# Power.net
KiCad netlist of a schematic drawn in Altium Designer
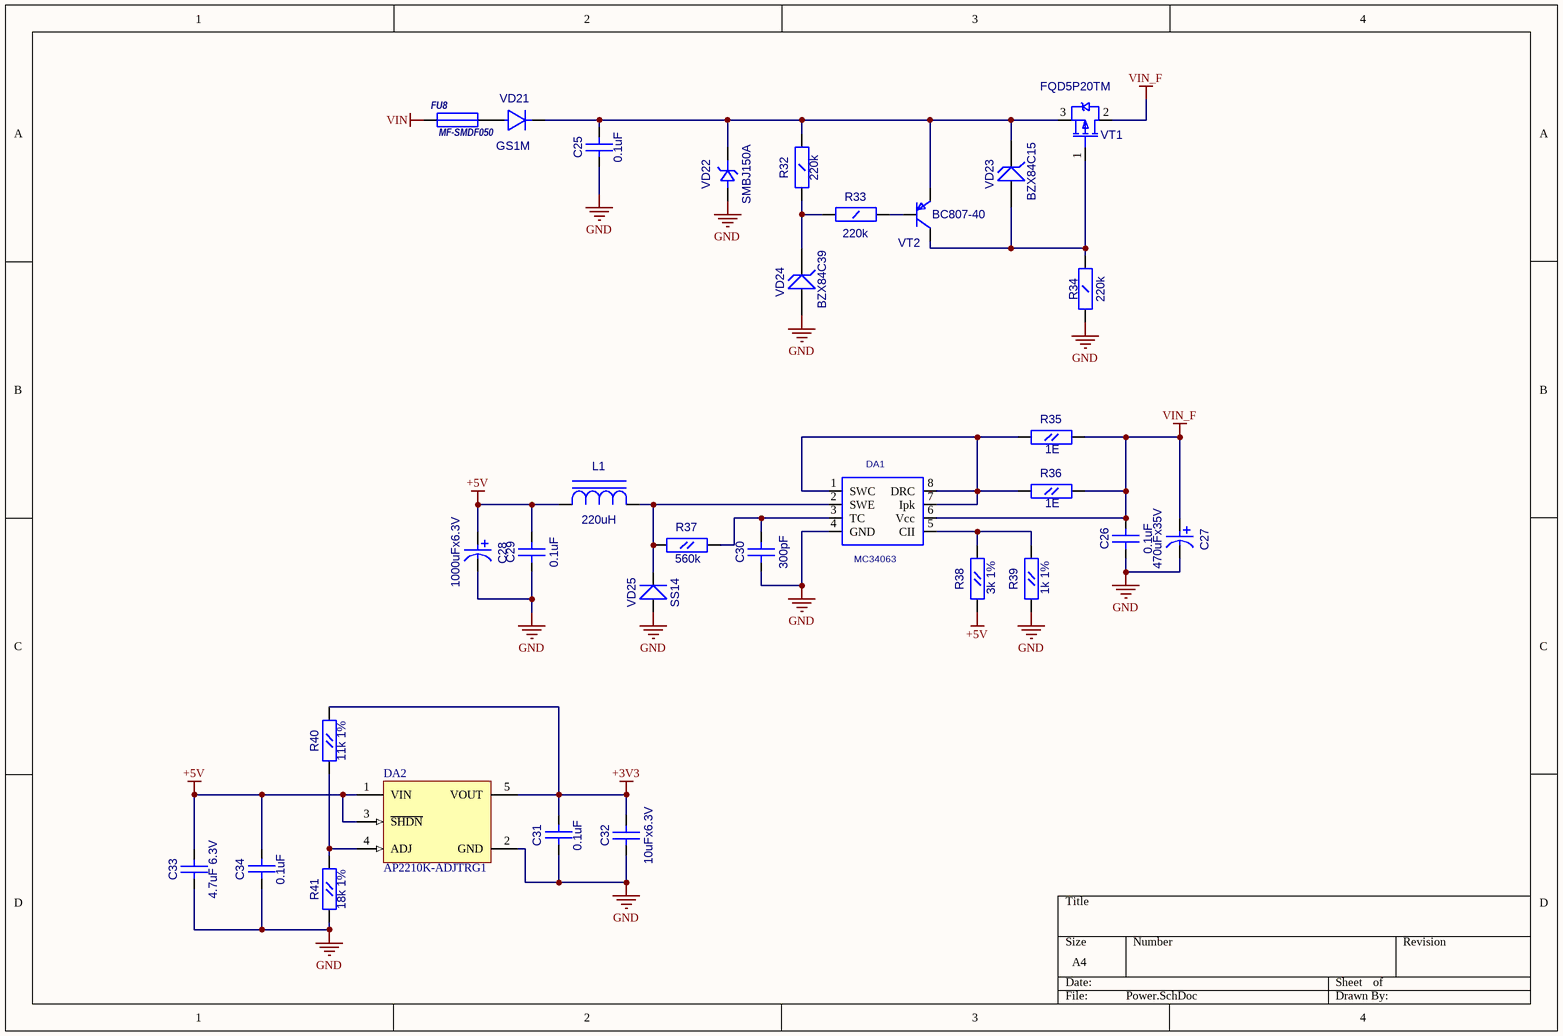
[diagram p0: Power.SchDoc]

(export (version "E")
  (design (tool "Eeschema 10.0.6"))
  (components
    (comp (ref "C25")
      (value "0.1uF")
      (footprint "CC1206")
      (description "CC1206")
      (libsource (lib "gprs_modem_2") (part "CC1206"))
    )
    (comp (ref "C26")
      (value "0.1uF")
      (footprint "CC0603")
      (description "CC0603")
      (libsource (lib "gprs_modem_2") (part "CC0603"))
    )
    (comp (ref "C27")
      (value "470uFx35V")
      (footprint "CC16X10_CAP0.5(1)(Primary)")
      (description "CAP0.5(1)")
      (libsource (lib "gprs_modem_2") (part "CAP0.5(1)"))
    )
    (comp (ref "C28")
      (value "1000uFx6.3V")
      (footprint "CC8X3.5")
      (description "CAP0.35")
      (libsource (lib "gprs_modem_2") (part "CAP0.35"))
    )
    (comp (ref "C29")
      (value "0.1uF")
      (footprint "CC0603")
      (description "CC0603")
      (libsource (lib "gprs_modem_2") (part "CC0603"))
    )
    (comp (ref "C30")
      (value "300pF")
      (footprint "CC0603")
      (description "CC0603")
      (libsource (lib "gprs_modem_2") (part "CC0603"))
    )
    (comp (ref "C31")
      (value "0.1uF")
      (footprint "CC0603")
      (description "CC0603")
      (libsource (lib "gprs_modem_2") (part "CC0603"))
    )
    (comp (ref "C32")
      (value "10uFx6.3V")
      (footprint "CC0805")
      (description "CC0805")
      (libsource (lib "gprs_modem_2") (part "CC0805"))
    )
    (comp (ref "C33")
      (value "4.7uF 6.3V")
      (footprint "CC0805")
      (description "CC0805")
      (libsource (lib "gprs_modem_2") (part "CC0805"))
    )
    (comp (ref "C34")
      (value "0.1uF")
      (footprint "CC0603")
      (description "CC0603")
      (libsource (lib "gprs_modem_2") (part "CC0603"))
    )
    (comp (ref "DA1") (value "MC34063") (footprint "SO-8") (libsource (lib "Schetchik") (part "MC34063")))
    (comp (ref "DA2")
      (value "AP2210K-ADJTRG1")
      (footprint "SOT23-5")
      (fields (field (name "PUBLISHER") "Altium Limited"))
      (libsource (lib "gprs_modem_2") (part "MCP1824T-ADJE/OT"))
    )
    (comp (ref "FU8")
      (value "MF-SMDF050")
      (footprint "MF-SMDF")
      (description "MF-SMDF")
      (libsource (lib "gprs_modem_2") (part "MF-SMDF"))
    )
    (comp (ref "L1")
      (value "220uH")
      (footprint "SDR0805")
      (description "SDR0805")
      (libsource (lib "gprs_modem_2") (part "SDR0805"))
    )
    (comp (ref "R32")
      (value "220k")
      (footprint "RC1206")
      (description "RC1206")
      (libsource (lib "gprs_modem_2") (part "RC1206"))
    )
    (comp (ref "R33")
      (value "220k")
      (footprint "RC1206")
      (description "RC1206")
      (libsource (lib "gprs_modem_2") (part "RC1206"))
    )
    (comp (ref "R34")
      (value "220k")
      (footprint "RC1206")
      (description "RC1206")
      (libsource (lib "gprs_modem_2") (part "RC1206"))
    )
    (comp (ref "R35")
      (value "1E")
      (footprint "RC0805")
      (description "RC0805")
      (libsource (lib "gprs_modem_2") (part "RC0805"))
    )
    (comp (ref "R36")
      (value "1E")
      (footprint "RC0805")
      (description "RC0805")
      (libsource (lib "gprs_modem_2") (part "RC0805"))
    )
    (comp (ref "R37")
      (value "560k")
      (footprint "RC0603")
      (description "RC0603")
      (libsource (lib "gprs_modem_2") (part "RC0603"))
    )
    (comp (ref "R38")
      (value "3k 1%")
      (footprint "RC0603")
      (description "RC0603")
      (libsource (lib "gprs_modem_2") (part "RC0603"))
    )
    (comp (ref "R39")
      (value "1k 1%")
      (footprint "RC0603")
      (description "RC0603")
      (libsource (lib "gprs_modem_2") (part "RC0603"))
    )
    (comp (ref "R40")
      (value "11k 1%")
      (footprint "RC0603")
      (description "RC0603")
      (libsource (lib "gprs_modem_2") (part "RC0603"))
    )
    (comp (ref "R41")
      (value "18k 1%")
      (footprint "RC0603")
      (description "RC0603")
      (libsource (lib "gprs_modem_2") (part "RC0603"))
    )
    (comp (ref "VD21") (value "GS1M") (footprint "SMA") (libsource (lib "gprs_modem") (part "GS1M")))
    (comp (ref "VD22")
      (value "SMBJ150A")
      (footprint "SMB")
      (description "SMBJ")
      (libsource (lib "gprs_modem_2") (part "SMBJ"))
    )
    (comp (ref "VD23")
      (value "BZX84C15")
      (footprint "SOT-23(123)")
      (description "Zener Voltage Regulator Diode")
      (libsource (lib "gprs_modem_2") (part "BZX84"))
    )
    (comp (ref "VD24")
      (value "BZX84C39")
      (footprint "SOT-23(123)")
      (description "Zener Voltage Regulator Diode")
      (libsource (lib "gprs_modem_2") (part "BZX84"))
    )
    (comp (ref "VD25")
      (value "SS14")
      (footprint "SMA")
      (description "Schottky Rectifier")
      (libsource (lib "gprs_modem_2") (part "SS14"))
    )
    (comp (ref "VT1")
      (value "FQD5P20TM")
      (footprint "D-PAK(TO-252AA)")
      (description "HEXFET Power MOSFET")
      (libsource (lib "gprs_modem_2") (part "IRFR9220"))
    )
    (comp (ref "VT2")
      (value "BC807-40")
      (footprint "SOT-23(123)")
      (description "BC857B")
      (libsource (lib "gprs_modem") (part "BC857B"))
    )
  )
  (nets
    (net (code "1") (name "+3V3") (class "Default")
      (node (ref "C31") (pin "1") (pinfunction "A_1") (pintype "passive"))
      (node (ref "C32") (pin "2") (pinfunction "B_2") (pintype "passive"))
      (node (ref "DA2") (pin "5") (pinfunction "VOUT_5") (pintype "power_in"))
      (node (ref "R40") (pin "2") (pinfunction "B_2") (pintype "passive"))
    )
    (net (code "2") (name "+5V") (class "Default")
      (node (ref "C28") (pin "1") (pintype "passive"))
      (node (ref "C29") (pin "2") (pinfunction "B_2") (pintype "passive"))
      (node (ref "C33") (pin "2") (pinfunction "B_2") (pintype "passive"))
      (node (ref "C34") (pin "1") (pinfunction "A_1") (pintype "passive"))
      (node (ref "DA2") (pin "1") (pinfunction "VIN_1") (pintype "power_in"))
      (node (ref "DA2") (pin "3") (pinfunction "~{SHDN}_3") (pintype "input"))
      (node (ref "L1") (pin "1") (pinfunction "C_1") (pintype "passive"))
      (node (ref "R38") (pin "1") (pinfunction "A_1") (pintype "passive"))
    )
    (net (code "3") (name "GND") (class "Default")
      (node (ref "C25") (pin "1") (pinfunction "A_1") (pintype "passive"))
      (node (ref "C26") (pin "1") (pinfunction "A_1") (pintype "passive"))
      (node (ref "C27") (pin "1") (pintype "passive"))
      (node (ref "C28") (pin "2") (pintype "passive"))
      (node (ref "C29") (pin "1") (pinfunction "A_1") (pintype "passive"))
      (node (ref "C30") (pin "1") (pinfunction "A_1") (pintype "passive"))
      (node (ref "C31") (pin "2") (pinfunction "B_2") (pintype "passive"))
      (node (ref "C32") (pin "1") (pinfunction "A_1") (pintype "passive"))
      (node (ref "C33") (pin "1") (pinfunction "A_1") (pintype "passive"))
      (node (ref "C34") (pin "2") (pinfunction "B_2") (pintype "passive"))
      (node (ref "DA1") (pin "4") (pinfunction "GND_4") (pintype "passive"))
      (node (ref "DA2") (pin "2") (pinfunction "GND_2") (pintype "power_in"))
      (node (ref "R34") (pin "2") (pinfunction "B_2") (pintype "passive"))
      (node (ref "R39") (pin "1") (pinfunction "A_1") (pintype "passive"))
      (node (ref "R41") (pin "1") (pinfunction "A_1") (pintype "passive"))
      (node (ref "VD22") (pin "1") (pinfunction "A_1") (pintype "passive"))
      (node (ref "VD24") (pin "1") (pinfunction "A_1") (pintype "passive"))
      (node (ref "VD25") (pin "1") (pinfunction "A_1") (pintype "passive"))
    )
    (net (code "4") (name "Net-(C25-B)") (class "Default")
      (node (ref "C25") (pin "2") (pinfunction "B_2") (pintype "passive"))
      (node (ref "R32") (pin "2") (pinfunction "B_2") (pintype "passive"))
      (node (ref "VD21") (pin "2") (pinfunction "K_2") (pintype "passive"))
      (node (ref "VD22") (pin "2") (pinfunction "K_2") (pintype "passive"))
      (node (ref "VD23") (pin "3") (pinfunction "K_3") (pintype "passive"))
      (node (ref "VT1") (pin "3") (pinfunction "S_3") (pintype "passive"))
      (node (ref "VT2") (pin "2") (pinfunction "E_2") (pintype "passive"))
    )
    (net (code "5") (name "Net-(C30-B)") (class "Default")
      (node (ref "C30") (pin "2") (pinfunction "B_2") (pintype "passive"))
      (node (ref "DA1") (pin "3") (pinfunction "TC_3") (pintype "passive"))
      (node (ref "R37") (pin "2") (pinfunction "B_2") (pintype "passive"))
    )
    (net (code "6") (name "Net-(DA1-CII)") (class "Default")
      (node (ref "DA1") (pin "5") (pinfunction "CII_5") (pintype "passive"))
      (node (ref "R38") (pin "2") (pinfunction "B_2") (pintype "passive"))
      (node (ref "R39") (pin "2") (pinfunction "B_2") (pintype "passive"))
    )
    (net (code "7") (name "Net-(DA1-DRC)") (class "Default")
      (node (ref "DA1") (pin "1") (pinfunction "SWC_1") (pintype "passive"))
      (node (ref "DA1") (pin "7") (pinfunction "Ipk_7") (pintype "passive"))
      (node (ref "DA1") (pin "8") (pinfunction "DRC_8") (pintype "passive"))
      (node (ref "R35") (pin "1") (pinfunction "A_1") (pintype "passive"))
      (node (ref "R36") (pin "1") (pinfunction "A_1") (pintype "passive"))
    )
    (net (code "8") (name "Net-(DA1-SWE)") (class "Default")
      (node (ref "DA1") (pin "2") (pinfunction "SWE_2") (pintype "passive"))
      (node (ref "L1") (pin "2") (pinfunction "A_2") (pintype "passive"))
      (node (ref "R37") (pin "1") (pinfunction "A_1") (pintype "passive"))
      (node (ref "VD25") (pin "2") (pinfunction "K_2") (pintype "passive"))
    )
    (net (code "9") (name "Net-(DA2-ADJ)") (class "Default")
      (node (ref "DA2") (pin "4") (pinfunction "ADJ_4") (pintype "input"))
      (node (ref "R40") (pin "1") (pinfunction "A_1") (pintype "passive"))
      (node (ref "R41") (pin "2") (pinfunction "B_2") (pintype "passive"))
    )
    (net (code "10") (name "Net-(R32-A)") (class "Default")
      (node (ref "R32") (pin "1") (pinfunction "A_1") (pintype "passive"))
      (node (ref "R33") (pin "1") (pinfunction "A_1") (pintype "passive"))
      (node (ref "VD24") (pin "3") (pinfunction "K_3") (pintype "passive"))
    )
    (net (code "11") (name "Net-(R33-B)") (class "Default")
      (node (ref "R33") (pin "2") (pinfunction "B_2") (pintype "passive"))
      (node (ref "VT2") (pin "1") (pinfunction "B_1") (pintype "passive"))
    )
    (net (code "12") (name "Net-(R34-A)") (class "Default")
      (node (ref "R34") (pin "1") (pinfunction "A_1") (pintype "passive"))
      (node (ref "VD23") (pin "1") (pinfunction "A_1") (pintype "passive"))
      (node (ref "VT1") (pin "1") (pinfunction "G_1") (pintype "passive"))
      (node (ref "VT2") (pin "3") (pinfunction "C_3") (pintype "passive"))
    )
    (net (code "13") (name "Net-(VD21-A)") (class "Default")
      (node (ref "FU8") (pin "2") (pintype "passive"))
      (node (ref "VD21") (pin "1") (pinfunction "A_1") (pintype "passive"))
    )
    (net (code "14") (name "VIN") (class "Default") (node (ref "FU8") (pin "1") (pintype "passive")))
    (net (code "15") (name "VIN_F") (class "Default")
      (node (ref "C26") (pin "2") (pinfunction "B_2") (pintype "passive"))
      (node (ref "C27") (pin "2") (pintype "passive"))
      (node (ref "DA1") (pin "6") (pinfunction "Vcc_6") (pintype "passive"))
      (node (ref "R35") (pin "2") (pinfunction "B_2") (pintype "passive"))
      (node (ref "R36") (pin "2") (pinfunction "B_2") (pintype "passive"))
      (node (ref "VT1") (pin "2") (pinfunction "D_2") (pintype "passive"))
    )
  )
)
